# Power_Supply_Unit.net
KiCad netlist of a schematic drawn in Altium Designer
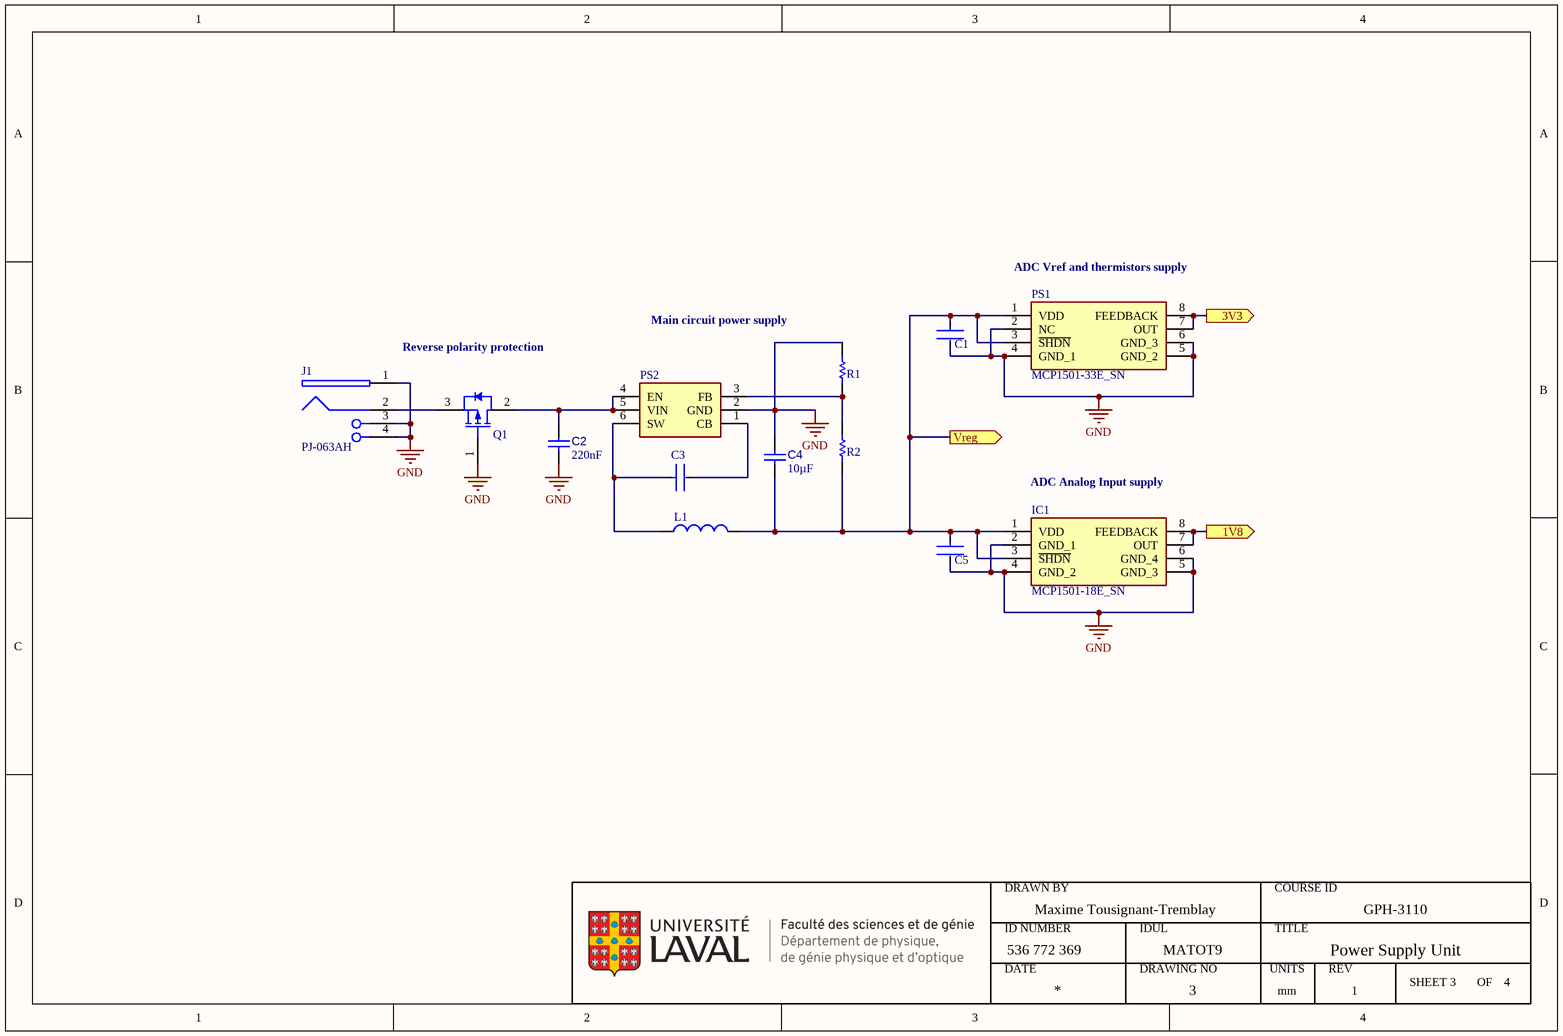
[diagram p0: Power Supply Unit.SchDoc]

(export (version "E")
  (design (tool "Eeschema 10.0.6"))
  (components
    (comp (ref "*1")
      (value "ULaval FSG-DPGPO")
      (libsource (lib "ULaval Title Block") (part "ULaval FSG-DPGPO"))
    )
    (comp (ref "C1")
      (value "CL10A225KO8NNNC")
      (footprint "FP-CL10-IPC_A")
      (description "Cap Ceramic 2.2uF 16V X5R ±10% Pad SMD 0603 +85°C T/R")
      (fields (field (name "TOLERANCE") "10%") (field (name "VOLTAGE") "16V"))
      (libsource (lib "Altium Content Vault") (part "b4654b650e69147ec39a6b967a45e02"))
    )
    (comp (ref "C2")
      (value "220nF")
      (footprint "CAPC0402(1005)60_L")
      (description "Chip Capacitor, 220nF +/-20%, 10V, 0402, Thickness 0.6 mm")
      (fields (field (name "TOLERANCE") "10%") (field (name "Comment") "Capacitor 220nF +/-20% 10V 0402"))
      (libsource (lib "Laval University") (part "CAP-NP-2"))
    )
    (comp (ref "C3")
      (value "CC0603KRX7R9BB104")
      (footprint "FP-CC0603-DA-MFG")
      (description "CAP CER 0.1UF 50V X7R 0603")
      (fields (field (name "MANUFACTURER") "YAGEO") (field (name "VOLTAGE") "50 V"))
      (libsource (lib "Altium Content Vault") (part "11868f565c42a9108669ba33697ecf6"))
    )
    (comp (ref "C4")
      (value "10µF")
      (footprint "CAPC2013X135X45NL10T25")
      (description "Chip Capacitor, 10 uF, +/- 10%, 16 V, 0805 (2012 Metric)")
      (fields (field (name "TOLERANCE") "10%") (field (name "Comment") "Capacitor 10 uF +/- 10% 16 V 0805"))
      (libsource (lib "Laval University") (part "CAP-NP-2"))
    )
    (comp (ref "C5")
      (value "CL10A225KO8NNNC")
      (footprint "FP-CL10-IPC_A")
      (description "Cap Ceramic 2.2uF 16V X5R ±10% Pad SMD 0603 +85°C T/R")
      (fields (field (name "TOLERANCE") "10%") (field (name "VOLTAGE") "16V"))
      (libsource (lib "Altium Content Vault") (part "b4654b650e69147ec39a6b967a45e02"))
    )
    (comp (ref "IC1")
      (value "MCP1501-18E_SN")
      (footprint "SamacSys:SOIC127P600X175-8N")
      (description "Integrated Circuit")
      (fields
        (field (name "MANUFACTURER_PART_NUMBER") "MCP1501-18E/SN")
        (field (name "MOUSER PART NUMBER") "579-MCP1501-18E/SN")
      )
      (libsource (lib "SamacSys") (part "MCP1501-18E_SN"))
    )
    (comp (ref "J1")
      (value "PJ-063AH")
      (footprint "CUI-PJ-063AH_V")
      (fields (field (name "MANUFACTURER") "CUIInc."))
      (libsource (lib "Altium Content Vault") (part "JACK-2CD2_A"))
    )
    (comp (ref "L1")
      (value "7447916")
      (footprint "SMD-1210")
      (description "SMD-Multilayer Inductor WE-MI, L = 4.70 µH")
      (libsource (lib "Altium Content Vault") (part "PAS-IND-INDUCTOR-2"))
    )
    (comp (ref "PS1")
      (value "MCP1501-33E_SN")
      (footprint "SamacSys:SOIC127P600X175-8N")
      (description "Power Supply")
      (fields
        (field (name "MANUFACTURER_PART_NUMBER") "MCP1501-33E/SN")
        (field (name "MOUSER PART NUMBER") "579-MCP1501-33E/SN")
      )
      (libsource (lib "SamacSys") (part "MCP1501-33E_SN"))
    )
    (comp (ref "PS2")
      (value "LMR50410YFQDBVRQ1")
      (footprint "SamacSys:SOT95P280X145-6N")
      (description "Power Supply")
      (fields (field (name "MOUSER PART NUMBER") "595-MR50410YFQDBVRQ1"))
      (libsource (lib "*") (part "LMR50410YFQDBVRQ1"))
    )
    (comp (ref "Q1")
      (value "IPD90P03P4-04")
      (footprint "INF-PG-TO252-3-11_N")
      (description "Single P-Channel 30 V 4.5 mOhm 100 nC OptiMOS Power Mosfet - TO-252-3-11")
      (libsource (lib "Laval University") (part "INF-MOSFET-P-3"))
    )
    (comp (ref "R1")
      (value "RC0402FR-1322K1L")
      (footprint "RESC1005X40X25ML05T10")
      (fields (field (name "MANUFACTURER") "Yageo / Phycomp"))
      (libsource (lib "Altium Content Vault") (part "RES"))
    )
    (comp (ref "R2")
      (value "RC0402FR-0788K7L")
      (footprint "RESC1005X40X25NL05T10")
      (fields (field (name "MANUFACTURER") "Yageo"))
      (libsource (lib "Altium Content Vault") (part "RES"))
    )
  )
  (nets
    (net (code "1") (name "/1V8") (class "Default")
      (node (ref "IC1") (pin "7") (pinfunction "OUT_7") (pintype "passive"))
      (node (ref "IC1") (pin "8") (pinfunction "FEEDBACK_8") (pintype "passive"))
    )
    (net (code "2") (name "/3V3") (class "Default")
      (node (ref "PS1") (pin "7") (pinfunction "OUT_7") (pintype "passive"))
      (node (ref "PS1") (pin "8") (pinfunction "FEEDBACK_8") (pintype "passive"))
    )
    (net (code "3") (name "/Vreg") (class "Default")
      (node (ref "C1") (pin "1") (pinfunction "1_1") (pintype "passive"))
      (node (ref "C4") (pin "1") (pinfunction "1_1") (pintype "passive"))
      (node (ref "C5") (pin "1") (pinfunction "1_1") (pintype "passive"))
      (node (ref "IC1") (pin "1") (pinfunction "VDD_1") (pintype "passive"))
      (node (ref "IC1") (pin "3") (pinfunction "~{SHDN}_3") (pintype "passive"))
      (node (ref "L1") (pin "2") (pinfunction "2_2") (pintype "passive"))
      (node (ref "PS1") (pin "1") (pinfunction "VDD_1") (pintype "passive"))
      (node (ref "PS1") (pin "3") (pinfunction "~{SHDN}_3") (pintype "passive"))
      (node (ref "R2") (pin "1") (pinfunction "1_1") (pintype "passive"))
    )
    (net (code "4") (name "GND") (class "Default")
      (node (ref "C1") (pin "2") (pinfunction "2_2") (pintype "passive"))
      (node (ref "C2") (pin "2") (pinfunction "2_2") (pintype "passive"))
      (node (ref "C4") (pin "2") (pinfunction "2_2") (pintype "passive"))
      (node (ref "C5") (pin "2") (pinfunction "2_2") (pintype "passive"))
      (node (ref "IC1") (pin "2") (pinfunction "GND_1_2") (pintype "passive"))
      (node (ref "IC1") (pin "4") (pinfunction "GND_2_4") (pintype "passive"))
      (node (ref "IC1") (pin "5") (pinfunction "GND_3_5") (pintype "passive"))
      (node (ref "IC1") (pin "6") (pinfunction "GND_4_6") (pintype "passive"))
      (node (ref "J1") (pin "1") (pinfunction "1_1") (pintype "passive"))
      (node (ref "J1") (pin "3") (pinfunction "SHLD_3") (pintype "passive"))
      (node (ref "J1") (pin "4") (pinfunction "SHLD_4") (pintype "passive"))
      (node (ref "PS1") (pin "2") (pinfunction "NC_2") (pintype "passive"))
      (node (ref "PS1") (pin "4") (pinfunction "GND_1_4") (pintype "passive"))
      (node (ref "PS1") (pin "5") (pinfunction "GND_2_5") (pintype "passive"))
      (node (ref "PS1") (pin "6") (pinfunction "GND_3_6") (pintype "passive"))
      (node (ref "PS2") (pin "2") (pinfunction "GND_2") (pintype "passive"))
      (node (ref "Q1") (pin "1") (pinfunction "GATE_1") (pintype "passive"))
      (node (ref "R1") (pin "2") (pinfunction "2_2") (pintype "passive"))
    )
    (net (code "5") (name "Net-(PS2-CB)") (class "Default")
      (node (ref "C3") (pin "2") (pinfunction "2_2") (pintype "passive"))
      (node (ref "PS2") (pin "1") (pinfunction "CB_1") (pintype "passive"))
    )
    (net (code "6") (name "Net-(PS2-EN)") (class "Default")
      (node (ref "C2") (pin "1") (pinfunction "1_1") (pintype "passive"))
      (node (ref "PS2") (pin "4") (pinfunction "EN_4") (pintype "passive"))
      (node (ref "PS2") (pin "5") (pinfunction "VIN_5") (pintype "passive"))
      (node (ref "Q1") (pin "2") (pinfunction "DRAIN_2") (pintype "passive"))
    )
    (net (code "7") (name "Net-(PS2-FB)") (class "Default")
      (node (ref "PS2") (pin "3") (pinfunction "FB_3") (pintype "passive"))
      (node (ref "R1") (pin "1") (pinfunction "1_1") (pintype "passive"))
      (node (ref "R2") (pin "2") (pinfunction "2_2") (pintype "passive"))
    )
    (net (code "8") (name "Net-(PS2-SW)") (class "Default")
      (node (ref "C3") (pin "1") (pinfunction "1_1") (pintype "passive"))
      (node (ref "L1") (pin "1") (pinfunction "1_1") (pintype "passive"))
      (node (ref "PS2") (pin "6") (pinfunction "SW_6") (pintype "passive"))
    )
    (net (code "9") (name "Net-(Q1-SOURCE)") (class "Default")
      (node (ref "J1") (pin "2") (pinfunction "2_2") (pintype "passive"))
      (node (ref "Q1") (pin "3") (pinfunction "SOURCE_3") (pintype "passive"))
    )
  )
)
